# design.net
KiCad netlist of a schematic drawn in EasyEDA Pro
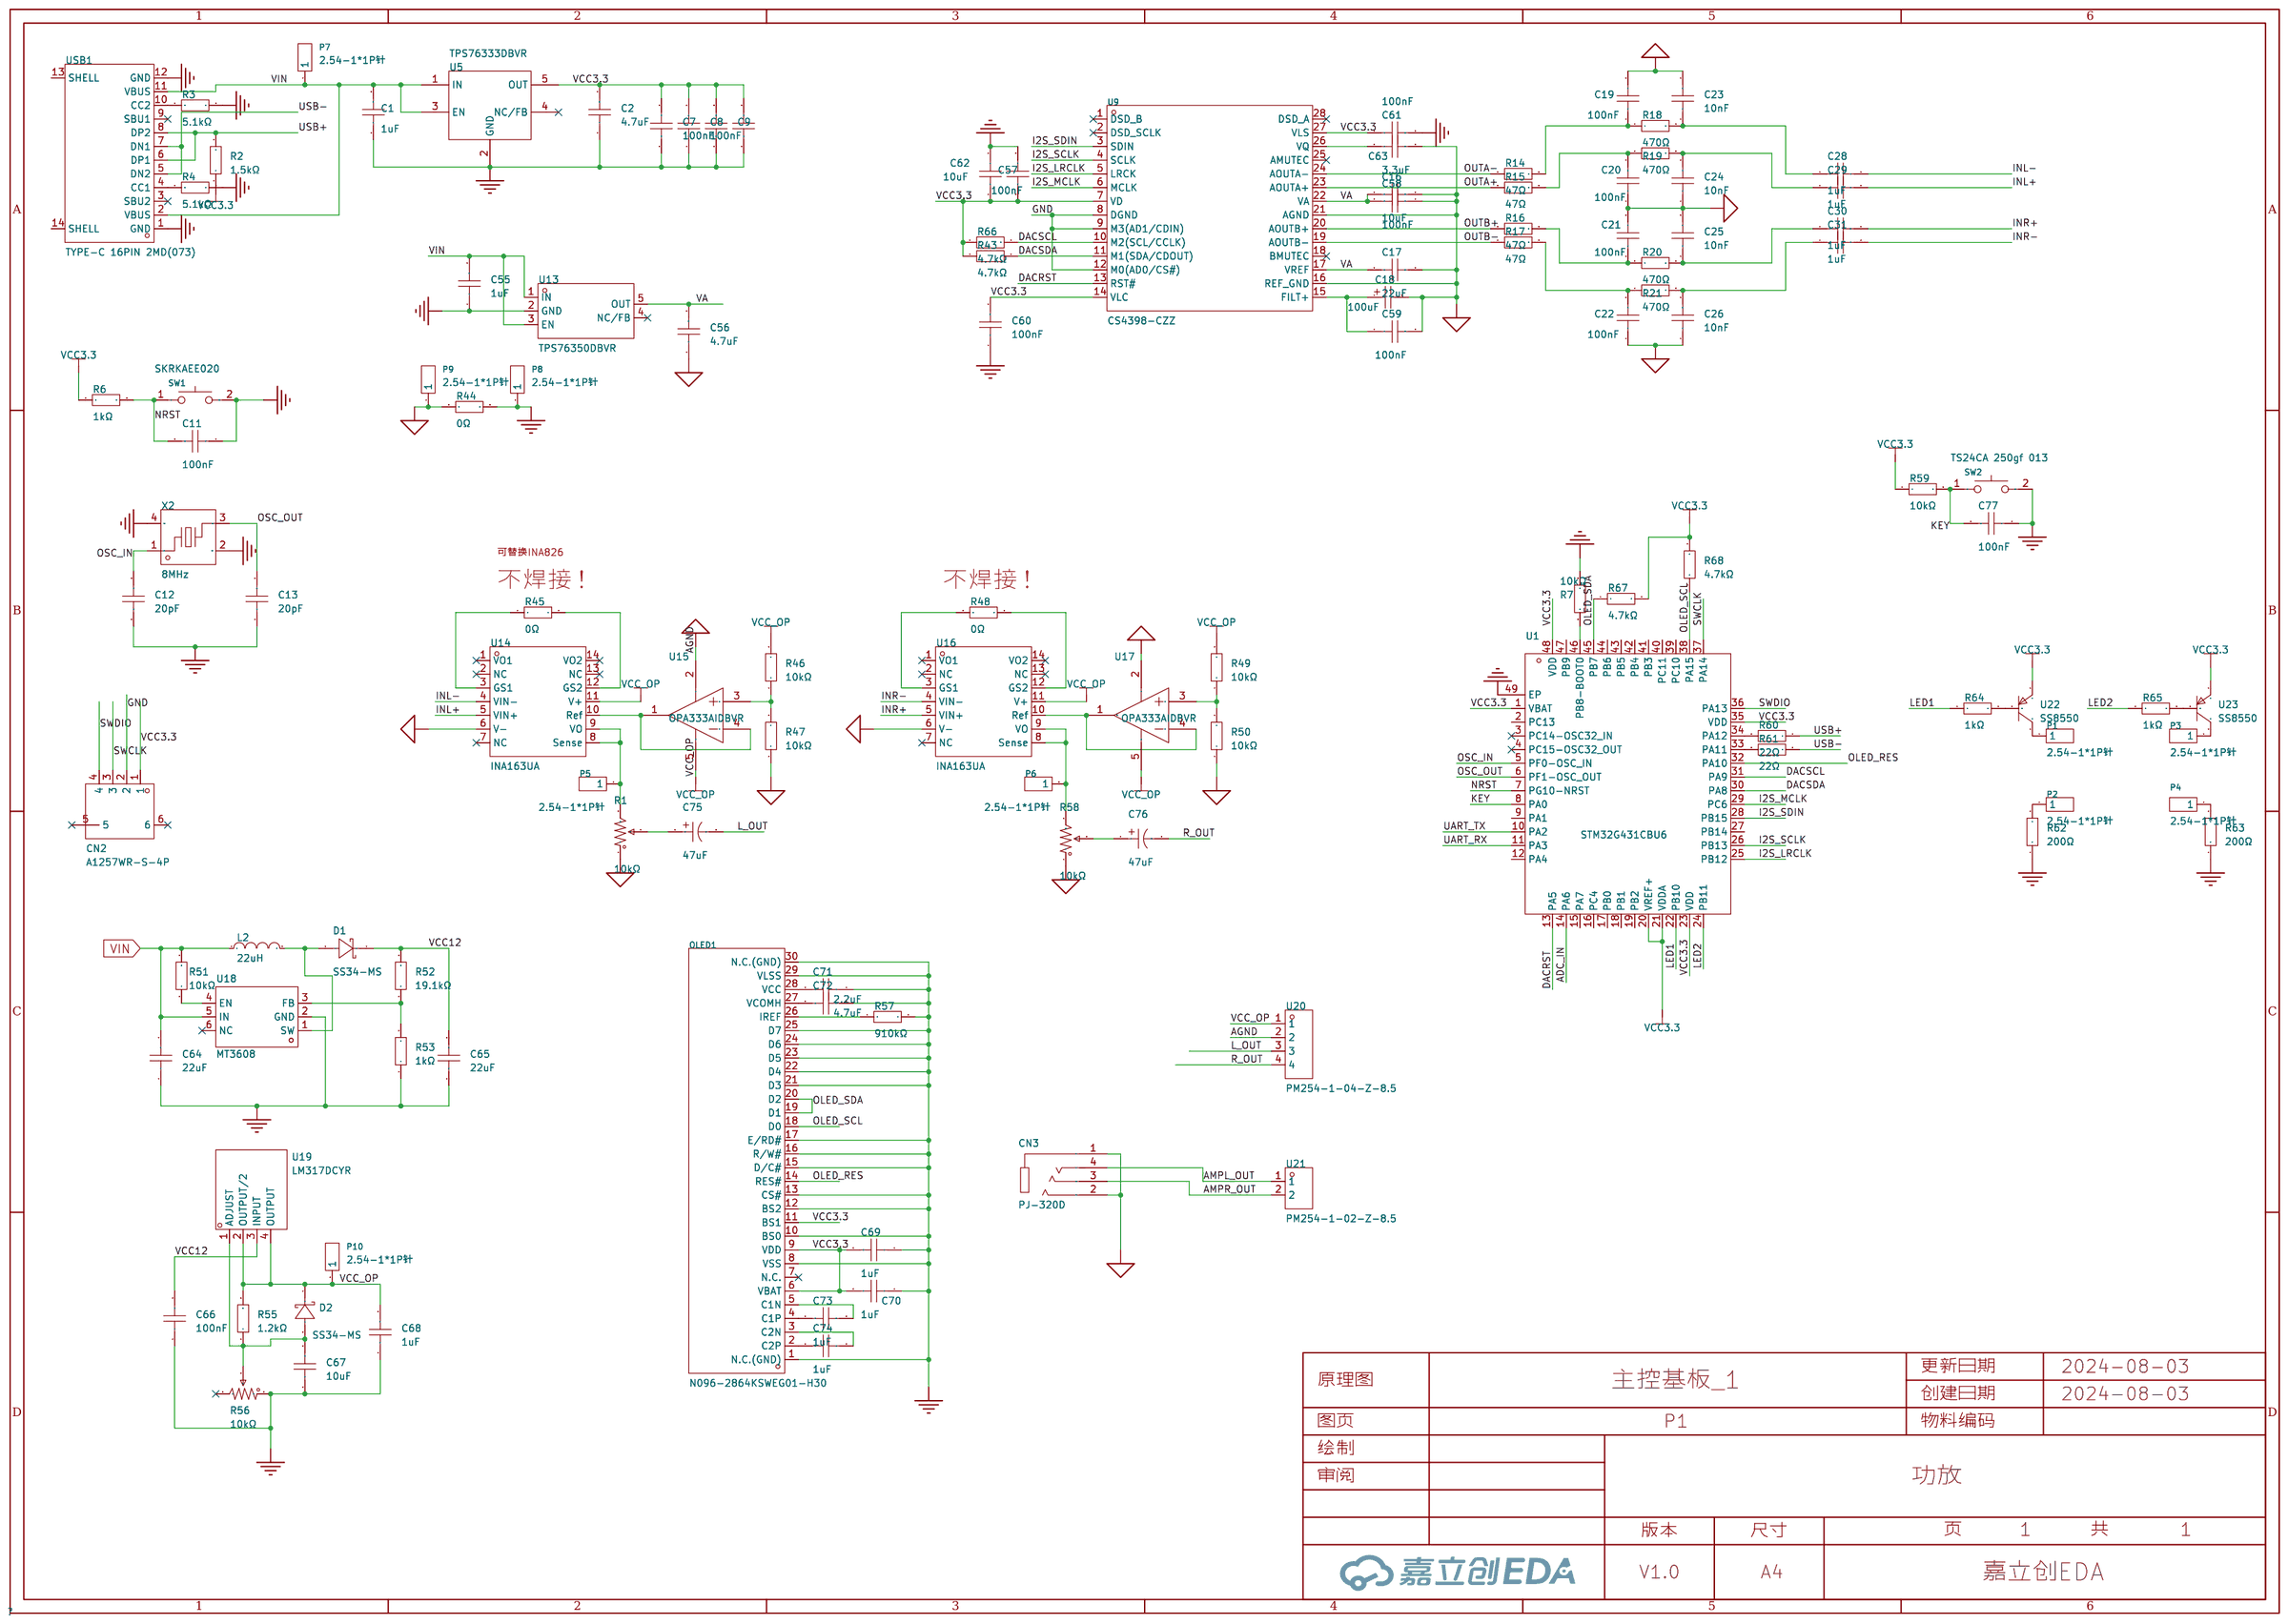
[diagram p0: schematic sheet]

(export (version "E")
  (design (tool "Eeschema 10.0.6"))
  (components
    (comp (ref "C1")
      (value "1uF")
      (fields
        (field (name "Manufacturer Part") "CL10A105KO8NNNC")
        (field (name "Manufacturer") "SAMSUNG(三星)")
      )
      (libsource (lib "easyedapro") (part "CapAcitance"))
    )
    (comp (ref "C2")
      (value "4.7uF")
      (fields
        (field (name "Manufacturer Part") "CL10A475KO8NNNC")
        (field (name "Manufacturer") "SAMSUNG(三星)")
      )
      (libsource (lib "easyedapro") (part "CapAcitance"))
    )
    (comp (ref "C7")
      (value "100nF")
      (fields
        (field (name "Manufacturer Part") "CC0603KRX7R9BB104")
        (field (name "Manufacturer") "YAGEO(国巨)")
      )
      (libsource (lib "easyedapro") (part "CapAcitance"))
    )
    (comp (ref "C8")
      (value "100nF")
      (fields
        (field (name "Manufacturer Part") "CC0603KRX7R9BB104")
        (field (name "Manufacturer") "YAGEO(国巨)")
      )
      (libsource (lib "easyedapro") (part "CapAcitance"))
    )
    (comp (ref "C9")
      (value "100nF")
      (fields
        (field (name "Manufacturer Part") "CC0603KRX7R9BB104")
        (field (name "Manufacturer") "YAGEO(国巨)")
      )
      (libsource (lib "easyedapro") (part "CapAcitance"))
    )
    (comp (ref "C10")
      (value "100nF")
      (fields
        (field (name "Manufacturer Part") "CC0603KRX7R9BB104")
        (field (name "Manufacturer") "YAGEO(国巨)")
      )
      (libsource (lib "easyedapro") (part "CapAcitance"))
    )
    (comp (ref "C11")
      (value "100nF")
      (fields
        (field (name "Manufacturer Part") "CC0603KRX7R9BB104")
        (field (name "Manufacturer") "YAGEO(国巨)")
      )
      (libsource (lib "easyedapro") (part "CapAcitance"))
    )
    (comp (ref "C12")
      (value "20pF")
      (fields
        (field (name "Manufacturer Part") "CC0603JRNPO9BN200")
        (field (name "Manufacturer") "YAGEO(国巨)")
      )
      (libsource (lib "easyedapro") (part "CapAcitance"))
    )
    (comp (ref "C13")
      (value "20pF")
      (fields
        (field (name "Manufacturer Part") "CC0603JRNPO9BN200")
        (field (name "Manufacturer") "YAGEO(国巨)")
      )
      (libsource (lib "easyedapro") (part "CapAcitance"))
    )
    (comp (ref "C16")
      (value "10uF")
      (fields
        (field (name "Manufacturer Part") "CL10A106KP8NNNC")
        (field (name "Manufacturer") "SAMSUNG(三星)")
      )
      (libsource (lib "easyedapro") (part "CapAcitance"))
    )
    (comp (ref "C17")
      (value "22uF")
      (fields
        (field (name "Manufacturer Part") "CL10A226MO7JZNC")
        (field (name "Manufacturer") "SAMSUNG(三星)")
      )
      (libsource (lib "easyedapro") (part "CapAcitance"))
    )
    (comp (ref "C18")
      (value "100uF")
      (fields
        (field (name "Manufacturer Part") "CA45-D-16V-100μF-K")
        (field (name "Manufacturer") "TORCH(火炬)")
      )
      (libsource (lib "easyedapro") (part "TAJD107K016RNJ"))
    )
    (comp (ref "C19")
      (value "100nF")
      (fields
        (field (name "Manufacturer Part") "CC0603KRX7R9BB104")
        (field (name "Manufacturer") "YAGEO(国巨)")
      )
      (libsource (lib "easyedapro") (part "CapAcitance"))
    )
    (comp (ref "C20")
      (value "100nF")
      (fields
        (field (name "Manufacturer Part") "CC0603KRX7R9BB104")
        (field (name "Manufacturer") "YAGEO(国巨)")
      )
      (libsource (lib "easyedapro") (part "CapAcitance"))
    )
    (comp (ref "C21")
      (value "100nF")
      (fields
        (field (name "Manufacturer Part") "CC0603KRX7R9BB104")
        (field (name "Manufacturer") "YAGEO(国巨)")
      )
      (libsource (lib "easyedapro") (part "CapAcitance"))
    )
    (comp (ref "C22")
      (value "100nF")
      (fields
        (field (name "Manufacturer Part") "CC0603KRX7R9BB104")
        (field (name "Manufacturer") "YAGEO(国巨)")
      )
      (libsource (lib "easyedapro") (part "CapAcitance"))
    )
    (comp (ref "C23")
      (value "10nF")
      (fields
        (field (name "Manufacturer Part") "CC0603KRX7R9BB103")
        (field (name "Manufacturer") "YAGEO(国巨)")
      )
      (libsource (lib "easyedapro") (part "CapAcitance"))
    )
    (comp (ref "C24")
      (value "10nF")
      (fields
        (field (name "Manufacturer Part") "CC0603KRX7R9BB103")
        (field (name "Manufacturer") "YAGEO(国巨)")
      )
      (libsource (lib "easyedapro") (part "CapAcitance"))
    )
    (comp (ref "C25")
      (value "10nF")
      (fields
        (field (name "Manufacturer Part") "CC0603KRX7R9BB103")
        (field (name "Manufacturer") "YAGEO(国巨)")
      )
      (libsource (lib "easyedapro") (part "CapAcitance"))
    )
    (comp (ref "C26")
      (value "10nF")
      (fields
        (field (name "Manufacturer Part") "CC0603KRX7R9BB103")
        (field (name "Manufacturer") "YAGEO(国巨)")
      )
      (libsource (lib "easyedapro") (part "CapAcitance"))
    )
    (comp (ref "C28")
      (value "1uF")
      (fields
        (field (name "Manufacturer Part") "CL10A105KO8NNNC")
        (field (name "Manufacturer") "SAMSUNG(三星)")
      )
      (libsource (lib "easyedapro") (part "CapAcitance"))
    )
    (comp (ref "C29")
      (value "1uF")
      (fields
        (field (name "Manufacturer Part") "CL10A105KO8NNNC")
        (field (name "Manufacturer") "SAMSUNG(三星)")
      )
      (libsource (lib "easyedapro") (part "CapAcitance"))
    )
    (comp (ref "C30")
      (value "1uF")
      (fields
        (field (name "Manufacturer Part") "CL10A105KO8NNNC")
        (field (name "Manufacturer") "SAMSUNG(三星)")
      )
      (libsource (lib "easyedapro") (part "CapAcitance"))
    )
    (comp (ref "C31")
      (value "1uF")
      (fields
        (field (name "Manufacturer Part") "CL10A105KO8NNNC")
        (field (name "Manufacturer") "SAMSUNG(三星)")
      )
      (libsource (lib "easyedapro") (part "CapAcitance"))
    )
    (comp (ref "C55")
      (value "1uF")
      (fields
        (field (name "Manufacturer Part") "CL10A105KO8NNNC")
        (field (name "Manufacturer") "SAMSUNG(三星)")
      )
      (libsource (lib "easyedapro") (part "CapAcitance"))
    )
    (comp (ref "C56")
      (value "4.7uF")
      (fields
        (field (name "Manufacturer Part") "CL10A475KO8NNNC")
        (field (name "Manufacturer") "SAMSUNG(三星)")
      )
      (libsource (lib "easyedapro") (part "CapAcitance"))
    )
    (comp (ref "C57")
      (value "100nF")
      (fields
        (field (name "Manufacturer Part") "CC0603KRX7R9BB104")
        (field (name "Manufacturer") "YAGEO(国巨)")
      )
      (libsource (lib "easyedapro") (part "CapAcitance"))
    )
    (comp (ref "C58")
      (value "100nF")
      (fields
        (field (name "Manufacturer Part") "CC0603KRX7R9BB104")
        (field (name "Manufacturer") "YAGEO(国巨)")
      )
      (libsource (lib "easyedapro") (part "CapAcitance"))
    )
    (comp (ref "C59")
      (value "100nF")
      (fields
        (field (name "Manufacturer Part") "CC0603KRX7R9BB104")
        (field (name "Manufacturer") "YAGEO(国巨)")
      )
      (libsource (lib "easyedapro") (part "CapAcitance"))
    )
    (comp (ref "C60")
      (value "100nF")
      (fields
        (field (name "Manufacturer Part") "CC0603KRX7R9BB104")
        (field (name "Manufacturer") "YAGEO(国巨)")
      )
      (libsource (lib "easyedapro") (part "CapAcitance"))
    )
    (comp (ref "C61")
      (value "100nF")
      (fields
        (field (name "Manufacturer Part") "CC0603KRX7R9BB104")
        (field (name "Manufacturer") "YAGEO(国巨)")
      )
      (libsource (lib "easyedapro") (part "CapAcitance"))
    )
    (comp (ref "C62")
      (value "10uF")
      (fields
        (field (name "Manufacturer Part") "CL10A106KP8NNNC")
        (field (name "Manufacturer") "SAMSUNG(三星)")
      )
      (libsource (lib "easyedapro") (part "CapAcitance"))
    )
    (comp (ref "C63")
      (value "3.3uF")
      (fields (field (name "Manufacturer Part") "C1608X5R1E335KT000E") (field (name "Manufacturer") "TDK"))
      (libsource (lib "easyedapro") (part "CapAcitance"))
    )
    (comp (ref "C64")
      (value "22uF")
      (fields
        (field (name "Manufacturer Part") "CL10A226MO7JZNC")
        (field (name "Manufacturer") "SAMSUNG(三星)")
      )
      (libsource (lib "easyedapro") (part "CapAcitance"))
    )
    (comp (ref "C65")
      (value "22uF")
      (fields
        (field (name "Manufacturer Part") "CL10A226MO7JZNC")
        (field (name "Manufacturer") "SAMSUNG(三星)")
      )
      (libsource (lib "easyedapro") (part "CapAcitance"))
    )
    (comp (ref "C66")
      (value "100nF")
      (fields
        (field (name "Manufacturer Part") "CC0603KRX7R9BB104")
        (field (name "Manufacturer") "YAGEO(国巨)")
      )
      (libsource (lib "easyedapro") (part "CapAcitance"))
    )
    (comp (ref "C67")
      (value "10uF")
      (fields
        (field (name "Manufacturer Part") "CL10A106MA8NRNC")
        (field (name "Manufacturer") "SAMSUNG(三星)")
      )
      (libsource (lib "easyedapro") (part "CapAcitance"))
    )
    (comp (ref "C68")
      (value "1uF")
      (fields
        (field (name "Manufacturer Part") "CL10A105KO8NNNC")
        (field (name "Manufacturer") "SAMSUNG(三星)")
      )
      (libsource (lib "easyedapro") (part "CapAcitance"))
    )
    (comp (ref "C69")
      (value "1uF")
      (fields
        (field (name "Manufacturer Part") "CL10A105KO8NNNC")
        (field (name "Manufacturer") "SAMSUNG(三星)")
      )
      (libsource (lib "easyedapro") (part "CapAcitance"))
    )
    (comp (ref "C70")
      (value "1uF")
      (fields
        (field (name "Manufacturer Part") "CL10A105KO8NNNC")
        (field (name "Manufacturer") "SAMSUNG(三星)")
      )
      (libsource (lib "easyedapro") (part "CapAcitance"))
    )
    (comp (ref "C71")
      (value "2.2uF")
      (fields
        (field (name "Manufacturer Part") "CL10A225KO8NNNC")
        (field (name "Manufacturer") "SAMSUNG(三星)")
      )
      (libsource (lib "easyedapro") (part "CapAcitance"))
    )
    (comp (ref "C72")
      (value "4.7uF")
      (fields
        (field (name "Manufacturer Part") "CL10A475KO8NNNC")
        (field (name "Manufacturer") "SAMSUNG(三星)")
      )
      (libsource (lib "easyedapro") (part "CapAcitance"))
    )
    (comp (ref "C73")
      (value "1uF")
      (fields
        (field (name "Manufacturer Part") "CL10A105KO8NNNC")
        (field (name "Manufacturer") "SAMSUNG(三星)")
      )
      (libsource (lib "easyedapro") (part "CapAcitance"))
    )
    (comp (ref "C74")
      (value "1uF")
      (fields
        (field (name "Manufacturer Part") "CL10A105KO8NNNC")
        (field (name "Manufacturer") "SAMSUNG(三星)")
      )
      (libsource (lib "easyedapro") (part "CapAcitance"))
    )
    (comp (ref "C75")
      (value "47uF")
      (footprint "easyedapro:CAP-SMD_BD5.0-L5.3-W5.3-LS6.0-FD")
      (description "容值:47uF;精度:±20%;额定电压:16V;纹波电流:31mA@120Hz;等效串联电阻:-;")
      (fields (field (name "Manufacturer Part") "RST47UF16V034") (field (name "Manufacturer") "KNSCHA(科尼盛)"))
      (libsource (lib "easyedapro") (part "RST47UF16V034"))
    )
    (comp (ref "C76")
      (value "47uF")
      (footprint "easyedapro:CAP-SMD_BD5.0-L5.3-W5.3-LS6.0-FD")
      (description "容值:47uF;精度:±20%;额定电压:16V;纹波电流:31mA@120Hz;等效串联电阻:-;")
      (fields (field (name "Manufacturer Part") "RST47UF16V034") (field (name "Manufacturer") "KNSCHA(科尼盛)"))
      (libsource (lib "easyedapro") (part "RST47UF16V034"))
    )
    (comp (ref "C77")
      (value "100nF")
      (fields
        (field (name "Manufacturer Part") "CC0603KRX7R9BB104")
        (field (name "Manufacturer") "YAGEO(国巨)")
      )
      (libsource (lib "easyedapro") (part "CapAcitance"))
    )
    (comp (ref "CN2")
      (value "A1257WR-S-4P")
      (footprint "easyedapro:CONN-SMD_A1257WR-S-4P")
      (description "插针结构:1x4P;间距:1.25mm;安装方式:-;行距:-;总PIN数:4P;排数:1;每排PIN数:4;参考系列:GH;触头材质:黄铜;")
      (fields (field (name "Manufacturer") "CJT(长江连接器)"))
      (libsource (lib "easyedapro") (part "A1257WR-S-4P"))
    )
    (comp (ref "CN3")
      (value "PJ-320D")
      (footprint "easyedapro:AUDIO-SMD_PJ-320D")
      (description "连接器类型:3.5mm耳机座;额定电流:300mA;额定电压:50V;工作温度范围:-16°C~+65°C;")
      (fields (field (name "Manufacturer") "SHOU HAN(首韩)"))
      (libsource (lib "easyedapro") (part "PJ-320D"))
    )
    (comp (ref "D1")
      (value "SS34-MS")
      (footprint "easyedapro:DO-214AC_L4.3-W2.7-LS5.0-RD")
      (description "二极管配置:-;正向压降(Vf):550mV@3A;直流反向耐压(Vr):40V;整流电流:3A;")
      (fields (field (name "Manufacturer") "MSKSEMI(美森科)"))
      (libsource (lib "easyedapro") (part "SS34-MS"))
    )
    (comp (ref "D2")
      (value "SS34-MS")
      (footprint "easyedapro:DO-214AC_L4.3-W2.7-LS5.0-RD")
      (description "二极管配置:-;正向压降(Vf):550mV@3A;直流反向耐压(Vr):40V;整流电流:3A;")
      (fields (field (name "Manufacturer") "MSKSEMI(美森科)"))
      (libsource (lib "easyedapro") (part "SS34-MS"))
    )
    (comp (ref "L2")
      (value "22uH")
      (footprint "easyedapro:IND-SMD_L3.0-W3.0_FNR30XXS")
      (description "电感值:22uH;精度:±20%;额定电流:690mA;饱和电流(Isat):680mA;")
      (fields (field (name "Manufacturer Part") "FNR3015S220MT") (field (name "Manufacturer") "cjiang(长江微电)"))
      (libsource (lib "easyedapro") (part "FNR3015S220MT"))
    )
    (comp (ref "OLED1")
      (value "N096-2864KSWEG01-H30")
      (footprint "easyedapro:OLED_0.96-30P-P0.70-12864")
      (description "主控芯片:SSD1306;尺寸(inch):0.96;")
      (fields (field (name "Manufacturer") "Newvision(新智景)"))
      (libsource (lib "easyedapro") (part "N096-2864KSWEG01-H30"))
    )
    (comp (ref "P1")
      (value "2.54-1*1P针")
      (footprint "easyedapro:HDR-TH_1P-P2.54-V-M")
      (description "插针结构:-;间距:-;行距:-;圆针/方针:-;安装类型:直插;排数:单排;总PIN位数:1P;额定电流:-;额定电压:-;配合针长度:-;塑高:-;触头材质:-;触头镀层:-;颜色:黑色;")
      (fields (field (name "Manufacturer") "BOOMELE(博穆精密)"))
      (libsource (lib "easyedapro") (part "Header-Male-2.54_1x1"))
    )
    (comp (ref "P2")
      (value "2.54-1*1P针")
      (footprint "easyedapro:HDR-TH_1P-P2.54-V-M")
      (description "插针结构:-;间距:-;行距:-;圆针/方针:-;安装类型:直插;排数:单排;总PIN位数:1P;额定电流:-;额定电压:-;配合针长度:-;塑高:-;触头材质:-;触头镀层:-;颜色:黑色;")
      (fields (field (name "Manufacturer") "BOOMELE(博穆精密)"))
      (libsource (lib "easyedapro") (part "Header-Male-2.54_1x1"))
    )
    (comp (ref "P3")
      (value "2.54-1*1P针")
      (footprint "easyedapro:HDR-TH_1P-P2.54-V-M")
      (description "插针结构:-;间距:-;行距:-;圆针/方针:-;安装类型:直插;排数:单排;总PIN位数:1P;额定电流:-;额定电压:-;配合针长度:-;塑高:-;触头材质:-;触头镀层:-;颜色:黑色;")
      (fields (field (name "Manufacturer") "BOOMELE(博穆精密)"))
      (libsource (lib "easyedapro") (part "Header-Male-2.54_1x1"))
    )
    (comp (ref "P4")
      (value "2.54-1*1P针")
      (footprint "easyedapro:HDR-TH_1P-P2.54-V-M")
      (description "插针结构:-;间距:-;行距:-;圆针/方针:-;安装类型:直插;排数:单排;总PIN位数:1P;额定电流:-;额定电压:-;配合针长度:-;塑高:-;触头材质:-;触头镀层:-;颜色:黑色;")
      (fields (field (name "Manufacturer") "BOOMELE(博穆精密)"))
      (libsource (lib "easyedapro") (part "Header-Male-2.54_1x1"))
    )
    (comp (ref "P5")
      (value "2.54-1*1P针")
      (footprint "easyedapro:HDR-TH_1P-P2.54-V-M")
      (description "插针结构:-;间距:-;行距:-;圆针/方针:-;安装类型:直插;排数:单排;总PIN位数:1P;额定电流:-;额定电压:-;配合针长度:-;塑高:-;触头材质:-;触头镀层:-;颜色:黑色;")
      (fields (field (name "Manufacturer") "BOOMELE(博穆精密)"))
      (libsource (lib "easyedapro") (part "Header-Male-2.54_1x1"))
    )
    (comp (ref "P6")
      (value "2.54-1*1P针")
      (footprint "easyedapro:HDR-TH_1P-P2.54-V-M")
      (description "插针结构:-;间距:-;行距:-;圆针/方针:-;安装类型:直插;排数:单排;总PIN位数:1P;额定电流:-;额定电压:-;配合针长度:-;塑高:-;触头材质:-;触头镀层:-;颜色:黑色;")
      (fields (field (name "Manufacturer") "BOOMELE(博穆精密)"))
      (libsource (lib "easyedapro") (part "Header-Male-2.54_1x1"))
    )
    (comp (ref "P7")
      (value "2.54-1*1P针")
      (footprint "easyedapro:HDR-TH_1P-P2.54-V-M")
      (description "插针结构:-;间距:-;行距:-;圆针/方针:-;安装类型:直插;排数:单排;总PIN位数:1P;额定电流:-;额定电压:-;配合针长度:-;塑高:-;触头材质:-;触头镀层:-;颜色:黑色;")
      (fields (field (name "Manufacturer") "BOOMELE(博穆精密)"))
      (libsource (lib "easyedapro") (part "Header-Male-2.54_1x1"))
    )
    (comp (ref "P8")
      (value "2.54-1*1P针")
      (footprint "easyedapro:HDR-TH_1P-P2.54-V-M")
      (description "插针结构:-;间距:-;行距:-;圆针/方针:-;安装类型:直插;排数:单排;总PIN位数:1P;额定电流:-;额定电压:-;配合针长度:-;塑高:-;触头材质:-;触头镀层:-;颜色:黑色;")
      (fields (field (name "Manufacturer") "BOOMELE(博穆精密)"))
      (libsource (lib "easyedapro") (part "Header-Male-2.54_1x1"))
    )
    (comp (ref "P9")
      (value "2.54-1*1P针")
      (footprint "easyedapro:HDR-TH_1P-P2.54-V-M")
      (description "插针结构:-;间距:-;行距:-;圆针/方针:-;安装类型:直插;排数:单排;总PIN位数:1P;额定电流:-;额定电压:-;配合针长度:-;塑高:-;触头材质:-;触头镀层:-;颜色:黑色;")
      (fields (field (name "Manufacturer") "BOOMELE(博穆精密)"))
      (libsource (lib "easyedapro") (part "Header-Male-2.54_1x1"))
    )
    (comp (ref "P10")
      (value "2.54-1*1P针")
      (footprint "easyedapro:HDR-TH_1P-P2.54-V-M")
      (description "插针结构:-;间距:-;行距:-;圆针/方针:-;安装类型:直插;排数:单排;总PIN位数:1P;额定电流:-;额定电压:-;配合针长度:-;塑高:-;触头材质:-;触头镀层:-;颜色:黑色;")
      (fields (field (name "Manufacturer") "BOOMELE(博穆精密)"))
      (libsource (lib "easyedapro") (part "Header-Male-2.54_1x1"))
    )
    (comp (ref "R1")
      (value "10kΩ")
      (footprint "easyedapro:RES-ADJ-SMD_3P-L3.0-W3.8-P1.75-BR")
      (description "阻值:10kΩ;精度:±25%;功率:150mW;温度系数:±250ppm/°C;")
      (fields (field (name "Manufacturer Part") "TC33X-2-103E") (field (name "Manufacturer") "BOURNS"))
      (libsource (lib "easyedapro") (part "TC33X-2-103E"))
    )
    (comp (ref "R2")
      (value "1.5kΩ")
      (fields (field (name "Manufacturer Part") "FRC0603F1501TS") (field (name "Manufacturer") "FOJAN(富捷)"))
      (libsource (lib "easyedapro") (part "电阻"))
    )
    (comp (ref "R3")
      (value "5.1kΩ")
      (fields (field (name "Manufacturer Part") "FRC0603F5101TS") (field (name "Manufacturer") "FOJAN(富捷)"))
      (libsource (lib "easyedapro") (part "电阻"))
    )
    (comp (ref "R4")
      (value "5.1kΩ")
      (fields (field (name "Manufacturer Part") "FRC0603F5101TS") (field (name "Manufacturer") "FOJAN(富捷)"))
      (libsource (lib "easyedapro") (part "电阻"))
    )
    (comp (ref "R6")
      (value "1kΩ")
      (fields
        (field (name "Manufacturer Part") "0603WAF1001T5E")
        (field (name "Manufacturer") "UNI-ROYAL(厚声)")
      )
      (libsource (lib "easyedapro") (part "电阻"))
    )
    (comp (ref "R7")
      (value "10kΩ")
      (fields
        (field (name "Manufacturer Part") "0603WAF1002T5E")
        (field (name "Manufacturer") "UNI-ROYAL(厚声)")
      )
      (libsource (lib "easyedapro") (part "电阻"))
    )
    (comp (ref "R14")
      (value "47Ω")
      (fields
        (field (name "Manufacturer Part") "0603WAJ0470T5E")
        (field (name "Manufacturer") "UNI-ROYAL(厚声)")
      )
      (libsource (lib "easyedapro") (part "电阻"))
    )
    (comp (ref "R15")
      (value "47Ω")
      (fields
        (field (name "Manufacturer Part") "0603WAJ0470T5E")
        (field (name "Manufacturer") "UNI-ROYAL(厚声)")
      )
      (libsource (lib "easyedapro") (part "电阻"))
    )
    (comp (ref "R16")
      (value "47Ω")
      (fields
        (field (name "Manufacturer Part") "0603WAJ0470T5E")
        (field (name "Manufacturer") "UNI-ROYAL(厚声)")
      )
      (libsource (lib "easyedapro") (part "电阻"))
    )
    (comp (ref "R17")
      (value "47Ω")
      (fields
        (field (name "Manufacturer Part") "0603WAJ0470T5E")
        (field (name "Manufacturer") "UNI-ROYAL(厚声)")
      )
      (libsource (lib "easyedapro") (part "电阻"))
    )
    (comp (ref "R18")
      (value "470Ω")
      (fields
        (field (name "Manufacturer Part") "0603WAJ0471T5E")
        (field (name "Manufacturer") "UNI-ROYAL(厚声)")
      )
      (libsource (lib "easyedapro") (part "电阻"))
    )
    (comp (ref "R19")
      (value "470Ω")
      (fields
        (field (name "Manufacturer Part") "0603WAJ0471T5E")
        (field (name "Manufacturer") "UNI-ROYAL(厚声)")
      )
      (libsource (lib "easyedapro") (part "电阻"))
    )
    (comp (ref "R20")
      (value "470Ω")
      (fields
        (field (name "Manufacturer Part") "0603WAJ0471T5E")
        (field (name "Manufacturer") "UNI-ROYAL(厚声)")
      )
      (libsource (lib "easyedapro") (part "电阻"))
    )
    (comp (ref "R21")
      (value "470Ω")
      (fields
        (field (name "Manufacturer Part") "0603WAJ0471T5E")
        (field (name "Manufacturer") "UNI-ROYAL(厚声)")
      )
      (libsource (lib "easyedapro") (part "电阻"))
    )
    (comp (ref "R43")
      (value "4.7kΩ")
      (fields (field (name "Manufacturer Part") "RC0603FR-074K7L") (field (name "Manufacturer") "YAGEO(国巨)"))
      (libsource (lib "easyedapro") (part "电阻"))
    )
    (comp (ref "R44")
      (value "0Ω")
      (fields
        (field (name "Manufacturer Part") "0603WAF0000T5E")
        (field (name "Manufacturer") "UNI-ROYAL(厚声)")
      )
      (libsource (lib "easyedapro") (part "电阻"))
    )
    (comp (ref "R45")
      (value "0Ω")
      (fields
        (field (name "Manufacturer Part") "0603WAF0000T5E")
        (field (name "Manufacturer") "UNI-ROYAL(厚声)")
      )
      (libsource (lib "easyedapro") (part "电阻"))
    )
    (comp (ref "R46")
      (value "10kΩ")
      (fields
        (field (name "Manufacturer Part") "0603WAF1002T5E")
        (field (name "Manufacturer") "UNI-ROYAL(厚声)")
      )
      (libsource (lib "easyedapro") (part "电阻"))
    )
    (comp (ref "R47")
      (value "10kΩ")
      (fields
        (field (name "Manufacturer Part") "0603WAF1002T5E")
        (field (name "Manufacturer") "UNI-ROYAL(厚声)")
      )
      (libsource (lib "easyedapro") (part "电阻"))
    )
    (comp (ref "R48")
      (value "0Ω")
      (fields
        (field (name "Manufacturer Part") "0603WAF0000T5E")
        (field (name "Manufacturer") "UNI-ROYAL(厚声)")
      )
      (libsource (lib "easyedapro") (part "电阻"))
    )
    (comp (ref "R49")
      (value "10kΩ")
      (fields
        (field (name "Manufacturer Part") "0603WAF1002T5E")
        (field (name "Manufacturer") "UNI-ROYAL(厚声)")
      )
      (libsource (lib "easyedapro") (part "电阻"))
    )
    (comp (ref "R50")
      (value "10kΩ")
      (fields
        (field (name "Manufacturer Part") "0603WAF1002T5E")
        (field (name "Manufacturer") "UNI-ROYAL(厚声)")
      )
      (libsource (lib "easyedapro") (part "电阻"))
    )
    (comp (ref "R51")
      (value "10kΩ")
      (fields
        (field (name "Manufacturer Part") "0603WAF1002T5E")
        (field (name "Manufacturer") "UNI-ROYAL(厚声)")
      )
      (libsource (lib "easyedapro") (part "电阻"))
    )
    (comp (ref "R52")
      (value "19.1kΩ")
      (fields
        (field (name "Manufacturer Part") "0603WAF1912T5E")
        (field (name "Manufacturer") "UNI-ROYAL(厚声)")
      )
      (libsource (lib "easyedapro") (part "电阻"))
    )
    (comp (ref "R53")
      (value "1kΩ")
      (fields
        (field (name "Manufacturer Part") "0603WAF1001T5E")
        (field (name "Manufacturer") "UNI-ROYAL(厚声)")
      )
      (libsource (lib "easyedapro") (part "电阻"))
    )
    (comp (ref "R55")
      (value "1.2kΩ")
      (fields
        (field (name "Manufacturer Part") "0603WAF1201T5E")
        (field (name "Manufacturer") "UNI-ROYAL(厚声)")
      )
      (libsource (lib "easyedapro") (part "电阻"))
    )
    (comp (ref "R56")
      (value "10kΩ")
      (footprint "easyedapro:RES-ADJ-SMD_3P-L3.0-W3.8-P1.75-BR")
      (description "阻值:10kΩ;精度:±25%;功率:150mW;温度系数:±250ppm/°C;")
      (fields (field (name "Manufacturer Part") "TC33X-2-103E") (field (name "Manufacturer") "BOURNS"))
      (libsource (lib "easyedapro") (part "TC33X-2-103E"))
    )
    (comp (ref "R57")
      (value "910kΩ")
      (fields
        (field (name "Manufacturer Part") "0603WAF9103T5E")
        (field (name "Manufacturer") "UNI-ROYAL(厚声)")
      )
      (libsource (lib "easyedapro") (part "电阻"))
    )
    (comp (ref "R58")
      (value "10kΩ")
      (footprint "easyedapro:RES-ADJ-SMD_3P-L3.0-W3.8-P1.75-BR")
      (description "阻值:10kΩ;精度:±25%;功率:150mW;温度系数:±250ppm/°C;")
      (fields (field (name "Manufacturer Part") "TC33X-2-103E") (field (name "Manufacturer") "BOURNS"))
      (libsource (lib "easyedapro") (part "TC33X-2-103E"))
    )
    (comp (ref "R59")
      (value "10kΩ")
      (fields
        (field (name "Manufacturer Part") "0603WAF1002T5E")
        (field (name "Manufacturer") "UNI-ROYAL(厚声)")
      )
      (libsource (lib "easyedapro") (part "电阻"))
    )
    (comp (ref "R60")
      (value "22Ω")
      (fields
        (field (name "Manufacturer Part") "0603WAF220JT5E")
        (field (name "Manufacturer") "UNI-ROYAL(厚声)")
      )
      (libsource (lib "easyedapro") (part "电阻"))
    )
    (comp (ref "R61")
      (value "22Ω")
      (fields
        (field (name "Manufacturer Part") "0603WAF220JT5E")
        (field (name "Manufacturer") "UNI-ROYAL(厚声)")
      )
      (libsource (lib "easyedapro") (part "电阻"))
    )
    (comp (ref "R62")
      (value "200Ω")
      (fields
        (field (name "Manufacturer Part") "0603WAF2000T5E")
        (field (name "Manufacturer") "UNI-ROYAL(厚声)")
      )
      (libsource (lib "easyedapro") (part "电阻"))
    )
    (comp (ref "R63")
      (value "200Ω")
      (fields
        (field (name "Manufacturer Part") "0603WAF2000T5E")
        (field (name "Manufacturer") "UNI-ROYAL(厚声)")
      )
      (libsource (lib "easyedapro") (part "电阻"))
    )
    (comp (ref "R64")
      (value "1kΩ")
      (fields
        (field (name "Manufacturer Part") "0603WAF1001T5E")
        (field (name "Manufacturer") "UNI-ROYAL(厚声)")
      )
      (libsource (lib "easyedapro") (part "电阻"))
    )
    (comp (ref "R65")
      (value "1kΩ")
      (fields
        (field (name "Manufacturer Part") "0603WAF1001T5E")
        (field (name "Manufacturer") "UNI-ROYAL(厚声)")
      )
      (libsource (lib "easyedapro") (part "电阻"))
    )
    (comp (ref "R66")
      (value "4.7kΩ")
      (fields (field (name "Manufacturer Part") "RC0603FR-074K7L") (field (name "Manufacturer") "YAGEO(国巨)"))
      (libsource (lib "easyedapro") (part "电阻"))
    )
    (comp (ref "R67")
      (value "4.7kΩ")
      (fields (field (name "Manufacturer Part") "RC0603FR-074K7L") (field (name "Manufacturer") "YAGEO(国巨)"))
      (libsource (lib "easyedapro") (part "电阻"))
    )
    (comp (ref "R68")
      (value "4.7kΩ")
      (fields (field (name "Manufacturer Part") "RC0603FR-074K7L") (field (name "Manufacturer") "YAGEO(国巨)"))
      (libsource (lib "easyedapro") (part "电阻"))
    )
    (comp (ref "SW1")
      (value "SKRKAEE020")
      (footprint "easyedapro:SW-SMD_L3.9-W3.0-P4.45")
      (description "电路结构:单刀单掷;按钮形状:圆形按钮;安装方式:立贴;开关长度:3.9mm;开关宽度:2.9mm;开关高度:2mm;触点电流:50mA;额定电压(DC):12V;带灯:-;机械寿命:-;")
      (fields (field (name "Manufacturer") "ALPSALPINE(阿尔卑斯阿尔派)"))
      (libsource (lib "easyedapro") (part "SKRKAEE020"))
    )
    (comp (ref "SW2")
      (value "TS24CA 250gf 013")
      (footprint "easyedapro:SW-SMD_L3.9-W3.0-P4.45")
      (description "电路结构:单刀单掷;按钮形状:圆形按钮;安装方式:立贴;开关长度:3.9mm;开关宽度:2.9mm;开关高度:2mm;触点电流:50mA;额定电压(DC):12V;带灯:-;机械寿命:-;")
      (fields (field (name "Manufacturer") "SHOU HAN(首韩)"))
      (libsource (lib "easyedapro") (part "SKRKAEE020"))
    )
    (comp (ref "U1")
      (value "STM32G431CBU6")
      (footprint "easyedapro:UFQFPN-48_L7.0-W7.0-P0.50-BL-EP")
      (description "CPU内核:ARM-M系列;程序存储容量:128KB;RAM总容量:32KB;GPIO端口数量:42;工作电压范围:1.71V~3.6V;CPU最大主频:170MHz;程序存储器类型:FLASH;")
      (fields (field (name "Manufacturer") "ST(意法半导体)"))
      (libsource (lib "easyedapro") (part "STM32G431CBU6"))
    )
    (comp (ref "U5")
      (value "TPS76333DBVR")
      (footprint "easyedapro:SOT-23-5_L3.0-W1.7-P0.95-LS2.8-BR")
      (description "输出类型:固定;最大输入电压:10V;输出电流:150mA;输出电压（最小值/固定值）:3.3V;")
      (fields (field (name "Manufacturer") "TI(德州仪器)"))
      (libsource (lib "easyedapro") (part "TPS76333DBVR"))
    )
    (comp (ref "U9")
      (value "CS4398-CZZ")
      (footprint "easyedapro:TSSOP-28_L9.7-W4.4-P0.65-LS6.4-BL")
      (description "接口类型:PCM；DSD;供电电压:3.1V~5.25V;分辨率(位):24;")
      (fields (field (name "Manufacturer") "Cirrus Logic(凌云)"))
      (libsource (lib "easyedapro") (part "CS4398-CZZ"))
    )
    (comp (ref "U13")
      (value "TPS76350DBVR")
      (footprint "easyedapro:SOT-23-5_L3.0-W1.7-P0.95-LS2.8-BR")
      (description "输出类型:固定;最大输入电压:10V;输出电压:5V;最大输出电流:150mA;电源纹波抑制比(PSRR):60dB@(1kHz);输出极性:正极;")
      (fields (field (name "Manufacturer") "TI(德州仪器)"))
      (libsource (lib "easyedapro") (part "TPS76350DBVR"))
    )
    (comp (ref "U14")
      (value "INA163UA")
      (footprint "easyedapro:SOIC-14_L8.7-W3.9-P1.27-LS6.0-BL")
      (description "放大器数:单路;输入偏置电流(Ib):2uA;输入失调电压(Vos):50uV;增益带宽积(GBP):-;压摆率(SR):15V/us;带宽(-3db):800kHz;")
      (fields (field (name "Manufacturer") "TI(德州仪器)"))
      (libsource (lib "easyedapro") (part "INA163UA"))
    )
    (comp (ref "U15")
      (value "OPA333AIDBVR")
      (fields (field (name "Manufacturer") "TI(德州仪器)"))
      (libsource (lib "easyedapro") (part "OPA237NA/3K"))
    )
    (comp (ref "U16")
      (value "INA163UA")
      (footprint "easyedapro:SOIC-14_L8.7-W3.9-P1.27-LS6.0-BL")
      (description "放大器数:单路;输入偏置电流(Ib):2uA;输入失调电压(Vos):50uV;增益带宽积(GBP):-;压摆率(SR):15V/us;带宽(-3db):800kHz;")
      (fields (field (name "Manufacturer") "TI(德州仪器)"))
      (libsource (lib "easyedapro") (part "INA163UA"))
    )
    (comp (ref "U17")
      (value "OPA333AIDBVR")
      (fields (field (name "Manufacturer") "TI(德州仪器)"))
      (libsource (lib "easyedapro") (part "OPA237NA/3K"))
    )
    (comp (ref "U18")
      (value "MT3608")
      (footprint "easyedapro:SOT-23-6_L2.9-W1.6-P0.95-LS2.8-BL")
      (description "功能类型:升压型;输入电压:2V~24V;输出电压:28V;输出电流(最大值):-;")
      (fields (field (name "Manufacturer") "西安航天民芯"))
      (libsource (lib "easyedapro") (part "MT3608"))
    )
    (comp (ref "U19")
      (value "LM317DCYR")
      (footprint "easyedapro:SOT-223-3_L6.5-W3.4-P2.30-LS7.0-BR")
      (description "输出类型:可调;最大输入电压:40V;输出电压:1.25V~37V;最大输出电流:1.5A;输出极性:正极;")
      (fields (field (name "Manufacturer") "TI(德州仪器)"))
      (libsource (lib "easyedapro") (part "LM317DCYR"))
    )
    (comp (ref "U20")
      (value "PM254-1-04-Z-8.5")
      (footprint "easyedapro:HDR-TH_4P-P2.54-V-F")
      (fields (field (name "Manufacturer") "HCTL(华灿天禄)"))
      (libsource (lib "easyedapro") (part "PM254-1-04-Z-8.5"))
    )
    (comp (ref "U21")
      (value "PM254-1-02-Z-8.5")
      (footprint "easyedapro:HDR-TH_2P-P2.54-V-F")
      (fields (field (name "Manufacturer") "HCTL(华灿天禄)"))
      (libsource (lib "easyedapro") (part "PM254-1-02-Z-8.5"))
    )
    (comp (ref "U22")
      (value "SS8550")
      (footprint "easyedapro:SOT-23-3_L2.9-W1.3-P1.90-LS2.4-BR")
      (description "晶体管类型:PNP;集电极电流(Ic):1.5A;集射极击穿电压(Vceo):25V;功率(Pd):300mW;直流电流增益(hFE@Ic,Vce):120@100mA,1.0V;")
      (fields (field (name "Manufacturer") "宏迦橙"))
      (libsource (lib "easyedapro") (part "SS8550_C7420371"))
    )
    (comp (ref "U23")
      (value "SS8550")
      (footprint "easyedapro:SOT-23-3_L2.9-W1.3-P1.90-LS2.4-BR")
      (description "晶体管类型:PNP;集电极电流(Ic):1.5A;集射极击穿电压(Vceo):25V;功率(Pd):300mW;直流电流增益(hFE@Ic,Vce):120@100mA,1.0V;")
      (fields (field (name "Manufacturer") "宏迦橙"))
      (libsource (lib "easyedapro") (part "SS8550_C7420371"))
    )
    (comp (ref "USB1")
      (value "TYPE-C 16PIN 2MD(073)")
      (footprint "easyedapro:USB-C-SMD_TYPE-C-6PIN-2MD-073")
      (description "连接器类型:Type-C;标准:-;公母:母;端口数量:1;触点数量:16P;安装方式:卧贴;额定电流 - 电源:5A;工作温度范围:-25°C~+85°C;")
      (fields (field (name "Manufacturer") "SHOU HAN(首韩)"))
      (libsource (lib "easyedapro") (part "TYPE-C 16PIN 2MD(073)"))
    )
    (comp (ref "X2")
      (value "8MHz")
      (footprint "easyedapro:CRYSTAL-SMD_4P-L3.2-W2.5-BL")
      (description "晶振类型:贴片晶振;频率:8MHz;常温频差:±10ppm;外接负载电容:20pF;频率稳定度(全温):±20ppm;")
      (fields (field (name "Manufacturer Part") "X32258MSB4SI") (field (name "Manufacturer") "YXC(扬兴晶振)"))
      (libsource (lib "easyedapro") (part "X32258MSB4SI"))
    )
  )
  (nets
    (net (code "1") (name "/ADC_IN") (class "Default")
      (node (ref "U1") (pin "14") (pinfunction "PA6_14") (pintype "unspecified"))
    )
    (net (code "2") (name "/AMPL_OUT") (class "Default")
      (node (ref "CN3") (pin "4") (pinfunction "4_4") (pintype "unspecified"))
      (node (ref "U21") (pin "1") (pinfunction "1_1") (pintype "unspecified"))
    )
    (net (code "3") (name "/AMPR_OUT") (class "Default")
      (node (ref "CN3") (pin "3") (pinfunction "3_3") (pintype "unspecified"))
      (node (ref "U21") (pin "2") (pinfunction "2_2") (pintype "unspecified"))
    )
    (net (code "4") (name "/DACRST") (class "Default")
      (node (ref "U1") (pin "13") (pinfunction "PA5_13") (pintype "unspecified"))
      (node (ref "U9") (pin "13") (pinfunction "RST#_13") (pintype "input"))
    )
    (net (code "5") (name "/DACSCL") (class "Default")
      (node (ref "R66") (pin "2") (pinfunction "2_2") (pintype "input"))
      (node (ref "U1") (pin "31") (pinfunction "PA9_31") (pintype "unspecified"))
      (node (ref "U9") (pin "10") (pinfunction "M2(SCL/CCLK)_10") (pintype "input"))
    )
    (net (code "6") (name "/DACSDA") (class "Default")
      (node (ref "R43") (pin "2") (pinfunction "2_2") (pintype "input"))
      (node (ref "U1") (pin "30") (pinfunction "PA8_30") (pintype "unspecified"))
      (node (ref "U9") (pin "11") (pinfunction "M1(SDA/CDOUT)_11") (pintype "input"))
    )
    (net (code "7") (name "/I2S_LRCLK") (class "Default")
      (node (ref "U1") (pin "25") (pinfunction "PB12_25") (pintype "unspecified"))
      (node (ref "U9") (pin "5") (pinfunction "LRCK_5") (pintype "input"))
    )
    (net (code "8") (name "/I2S_MCLK") (class "Default")
      (node (ref "U1") (pin "29") (pinfunction "PC6_29") (pintype "unspecified"))
      (node (ref "U9") (pin "6") (pinfunction "MCLK_6") (pintype "input"))
    )
    (net (code "9") (name "/I2S_SCLK") (class "Default")
      (node (ref "U1") (pin "26") (pinfunction "PB13_26") (pintype "unspecified"))
      (node (ref "U9") (pin "4") (pinfunction "SCLK_4") (pintype "input"))
    )
    (net (code "10") (name "/I2S_SDIN") (class "Default")
      (node (ref "U1") (pin "28") (pinfunction "PB15_28") (pintype "unspecified"))
      (node (ref "U9") (pin "3") (pinfunction "SDIN_3") (pintype "input"))
    )
    (net (code "11") (name "/INL+") (class "Default")
      (node (ref "C29") (pin "2") (pinfunction "2_2") (pintype "input"))
      (node (ref "U14") (pin "5") (pinfunction "VIN+_5") (pintype "unspecified"))
    )
    (net (code "12") (name "/INL-") (class "Default")
      (node (ref "C28") (pin "2") (pinfunction "2_2") (pintype "input"))
      (node (ref "U14") (pin "4") (pinfunction "VIN-_4") (pintype "unspecified"))
    )
    (net (code "13") (name "/INR+") (class "Default")
      (node (ref "C30") (pin "2") (pinfunction "2_2") (pintype "input"))
      (node (ref "U16") (pin "5") (pinfunction "VIN+_5") (pintype "unspecified"))
    )
    (net (code "14") (name "/INR-") (class "Default")
      (node (ref "C31") (pin "2") (pinfunction "2_2") (pintype "input"))
      (node (ref "U16") (pin "4") (pinfunction "VIN-_4") (pintype "unspecified"))
    )
    (net (code "15") (name "/KEY") (class "Default")
      (node (ref "C77") (pin "2") (pinfunction "2_2") (pintype "input"))
      (node (ref "R59") (pin "2") (pinfunction "2_2") (pintype "input"))
      (node (ref "SW2") (pin "1") (pinfunction "1_1") (pintype "input"))
      (node (ref "U1") (pin "8") (pinfunction "PA0_8") (pintype "unspecified"))
    )
    (net (code "16") (name "/LED1") (class "Default")
      (node (ref "R64") (pin "1") (pinfunction "1_1") (pintype "input"))
      (node (ref "U1") (pin "22") (pinfunction "PB10_22") (pintype "unspecified"))
    )
    (net (code "17") (name "/LED2") (class "Default")
      (node (ref "R65") (pin "1") (pinfunction "1_1") (pintype "input"))
      (node (ref "U1") (pin "24") (pinfunction "PB11_24") (pintype "unspecified"))
    )
    (net (code "18") (name "/L_OUT") (class "Default")
      (node (ref "C75") (pin "2") (pinfunction "2_2") (pintype "input"))
      (node (ref "U20") (pin "3") (pinfunction "3_3") (pintype "unspecified"))
    )
    (net (code "19") (name "/NRST") (class "Default")
      (node (ref "C11") (pin "2") (pinfunction "2_2") (pintype "input"))
      (node (ref "R6") (pin "2") (pinfunction "2_2") (pintype "input"))
      (node (ref "SW1") (pin "1") (pinfunction "1_1") (pintype "input"))
      (node (ref "U1") (pin "7") (pinfunction "PG10-NRST_7") (pintype "unspecified"))
    )
    (net (code "20") (name "/OLED_RES") (class "Default")
      (node (ref "OLED1") (pin "14") (pinfunction "RES#_14") (pintype "input"))
      (node (ref "U1") (pin "32") (pinfunction "PA10_32") (pintype "unspecified"))
    )
    (net (code "21") (name "/OLED_SCL") (class "Default")
      (node (ref "OLED1") (pin "18") (pinfunction "D0_18") (pintype "input"))
      (node (ref "R68") (pin "1") (pinfunction "1_1") (pintype "input"))
      (node (ref "U1") (pin "38") (pinfunction "PA15_38") (pintype "unspecified"))
    )
    (net (code "22") (name "/OLED_SDA") (class "Default")
      (node (ref "OLED1") (pin "19") (pinfunction "D1_19") (pintype "input"))
      (node (ref "OLED1") (pin "20") (pinfunction "D2_20") (pintype "input"))
      (node (ref "R67") (pin "1") (pinfunction "1_1") (pintype "input"))
      (node (ref "U1") (pin "45") (pinfunction "PB7_45") (pintype "unspecified"))
    )
    (net (code "23") (name "/OSC_IN") (class "Default")
      (node (ref "C12") (pin "2") (pinfunction "2_2") (pintype "input"))
      (node (ref "U1") (pin "5") (pinfunction "PF0-OSC_IN_5") (pintype "unspecified"))
      (node (ref "X2") (pin "1") (pinfunction "1_1") (pintype "input"))
    )
    (net (code "24") (name "/OSC_OUT") (class "Default")
      (node (ref "C13") (pin "2") (pinfunction "2_2") (pintype "input"))
      (node (ref "U1") (pin "6") (pinfunction "PF1-OSC_OUT_6") (pintype "unspecified"))
      (node (ref "X2") (pin "3") (pinfunction "3_3") (pintype "input"))
    )
    (net (code "25") (name "/OUTA+") (class "Default")
      (node (ref "R15") (pin "1") (pinfunction "1_1") (pintype "input"))
      (node (ref "U9") (pin "23") (pinfunction "AOUTA+_23") (pintype "input"))
    )
    (net (code "26") (name "/OUTA-") (class "Default")
      (node (ref "R14") (pin "1") (pinfunction "1_1") (pintype "input"))
      (node (ref "U9") (pin "24") (pinfunction "AOUTA-_24") (pintype "input"))
    )
    (net (code "27") (name "/OUTB+") (class "Default")
      (node (ref "R16") (pin "1") (pinfunction "1_1") (pintype "input"))
      (node (ref "U9") (pin "20") (pinfunction "AOUTB+_20") (pintype "input"))
    )
    (net (code "28") (name "/OUTB-") (class "Default")
      (node (ref "R17") (pin "1") (pinfunction "1_1") (pintype "input"))
      (node (ref "U9") (pin "19") (pinfunction "AOUTB-_19") (pintype "input"))
    )
    (net (code "29") (name "/R_OUT") (class "Default")
      (node (ref "C76") (pin "2") (pinfunction "2_2") (pintype "input"))
      (node (ref "U20") (pin "4") (pinfunction "4_4") (pintype "unspecified"))
    )
    (net (code "30") (name "/SWCLK") (class "Default")
      (node (ref "CN2") (pin "3") (pinfunction "3_3") (pintype "unspecified"))
      (node (ref "U1") (pin "37") (pinfunction "PA14_37") (pintype "unspecified"))
    )
    (net (code "31") (name "/SWDIO") (class "Default")
      (node (ref "CN2") (pin "4") (pinfunction "4_4") (pintype "unspecified"))
      (node (ref "U1") (pin "36") (pinfunction "PA13_36") (pintype "unspecified"))
    )
    (net (code "32") (name "/UART_RX") (class "Default")
      (node (ref "U1") (pin "11") (pinfunction "PA3_11") (pintype "unspecified"))
    )
    (net (code "33") (name "/UART_TX") (class "Default")
      (node (ref "U1") (pin "10") (pinfunction "PA2_10") (pintype "unspecified"))
    )
    (net (code "34") (name "/USB+") (class "Default")
      (node (ref "R2") (pin "2") (pinfunction "2_2") (pintype "input"))
      (node (ref "R60") (pin "1") (pinfunction "1_1") (pintype "input"))
      (node (ref "USB1") (pin "6") (pinfunction "DP1_6") (pintype "unspecified"))
      (node (ref "USB1") (pin "8") (pinfunction "DP2_8") (pintype "unspecified"))
    )
    (net (code "35") (name "/USB-") (class "Default")
      (node (ref "R61") (pin "1") (pinfunction "1_1") (pintype "input"))
      (node (ref "USB1") (pin "5") (pinfunction "DN2_5") (pintype "unspecified"))
      (node (ref "USB1") (pin "7") (pinfunction "DN1_7") (pintype "unspecified"))
    )
    (net (code "36") (name "/VA") (class "Default")
      (node (ref "C16") (pin "1") (pinfunction "1_1") (pintype "input"))
      (node (ref "C17") (pin "1") (pinfunction "1_1") (pintype "input"))
      (node (ref "C56") (pin "2") (pinfunction "2_2") (pintype "input"))
      (node (ref "C58") (pin "2") (pinfunction "2_2") (pintype "input"))
      (node (ref "U13") (pin "5") (pinfunction "OUT_5") (pintype "input"))
      (node (ref "U9") (pin "17") (pinfunction "VREF_17") (pintype "input"))
      (node (ref "U9") (pin "22") (pinfunction "VA_22") (pintype "input"))
    )
    (net (code "37") (name "/VCC12") (class "Default")
      (node (ref "C65") (pin "2") (pinfunction "2_2") (pintype "input"))
      (node (ref "C66") (pin "2") (pinfunction "2_2") (pintype "input"))
      (node (ref "D1") (pin "1") (pinfunction "A_1") (pintype "unspecified"))
      (node (ref "R52") (pin "2") (pinfunction "2_2") (pintype "input"))
      (node (ref "U19") (pin "3") (pinfunction "INPUT_3") (pintype "unspecified"))
    )
    (net (code "38") (name "AGND") (class "Default")
      (node (ref "C16") (pin "2") (pinfunction "2_2") (pintype "input"))
      (node (ref "C17") (pin "2") (pinfunction "2_2") (pintype "input"))
      (node (ref "C18") (pin "2") (pinfunction "2_2") (pintype "input"))
      (node (ref "C19") (pin "2") (pinfunction "2_2") (pintype "input"))
      (node (ref "C20") (pin "1") (pinfunction "1_1") (pintype "input"))
      (node (ref "C21") (pin "2") (pinfunction "2_2") (pintype "input"))
      (node (ref "C22") (pin "1") (pinfunction "1_1") (pintype "input"))
      (node (ref "C23") (pin "2") (pinfunction "2_2") (pintype "input"))
      (node (ref "C24") (pin "1") (pinfunction "1_1") (pintype "input"))
      (node (ref "C25") (pin "2") (pinfunction "2_2") (pintype "input"))
      (node (ref "C26") (pin "1") (pinfunction "1_1") (pintype "input"))
      (node (ref "C56") (pin "1") (pinfunction "1_1") (pintype "input"))
      (node (ref "C58") (pin "1") (pinfunction "1_1") (pintype "input"))
      (node (ref "C59") (pin "2") (pinfunction "2_2") (pintype "input"))
      (node (ref "C63") (pin "2") (pinfunction "2_2") (pintype "input"))
      (node (ref "CN3") (pin "1") (pinfunction "1_1") (pintype "unspecified"))
      (node (ref "CN3") (pin "2") (pinfunction "2_2") (pintype "unspecified"))
      (node (ref "P9") (pin "1") (pinfunction "1_1") (pintype "input"))
      (node (ref "R1") (pin "1") (pinfunction "1_1") (pintype "unspecified"))
      (node (ref "R44") (pin "1") (pinfunction "1_1") (pintype "input"))
      (node (ref "R47") (pin "1") (pinfunction "1_1") (pintype "input"))
      (node (ref "R50") (pin "1") (pinfunction "1_1") (pintype "input"))
      (node (ref "R58") (pin "1") (pinfunction "1_1") (pintype "unspecified"))
      (node (ref "U14") (pin "6") (pinfunction "V-_6") (pintype "unspecified"))
      (node (ref "U15") (pin "2") (pinfunction "V-_2") (pintype "unspecified"))
      (node (ref "U16") (pin "6") (pinfunction "V-_6") (pintype "unspecified"))
      (node (ref "U17") (pin "2") (pinfunction "V-_2") (pintype "unspecified"))
      (node (ref "U20") (pin "2") (pinfunction "2_2") (pintype "unspecified"))
      (node (ref "U9") (pin "16") (pinfunction "REF_GND_16") (pintype "input"))
      (node (ref "U9") (pin "21") (pinfunction "AGND_21") (pintype "input"))
    )
    (net (code "39") (name "GND") (class "Default")
      (node (ref "C1") (pin "1") (pinfunction "1_1") (pintype "input"))
      (node (ref "C10") (pin "1") (pinfunction "1_1") (pintype "input"))
      (node (ref "C11") (pin "1") (pinfunction "1_1") (pintype "input"))
      (node (ref "C12") (pin "1") (pinfunction "1_1") (pintype "input"))
      (node (ref "C13") (pin "1") (pinfunction "1_1") (pintype "input"))
      (node (ref "C2") (pin "1") (pinfunction "1_1") (pintype "input"))
      (node (ref "C55") (pin "1") (pinfunction "1_1") (pintype "input"))
      (node (ref "C57") (pin "2") (pinfunction "2_2") (pintype "input"))
      (node (ref "C60") (pin "1") (pinfunction "1_1") (pintype "input"))
      (node (ref "C61") (pin "2") (pinfunction "2_2") (pintype "input"))
      (node (ref "C62") (pin "2") (pinfunction "2_2") (pintype "input"))
      (node (ref "C64") (pin "1") (pinfunction "1_1") (pintype "input"))
      (node (ref "C65") (pin "1") (pinfunction "1_1") (pintype "input"))
      (node (ref "C66") (pin "1") (pinfunction "1_1") (pintype "input"))
      (node (ref "C67") (pin "1") (pinfunction "1_1") (pintype "input"))
      (node (ref "C68") (pin "1") (pinfunction "1_1") (pintype "input"))
      (node (ref "C69") (pin "1") (pinfunction "1_1") (pintype "input"))
      (node (ref "C7") (pin "1") (pinfunction "1_1") (pintype "input"))
      (node (ref "C70") (pin "1") (pinfunction "1_1") (pintype "input"))
      (node (ref "C71") (pin "1") (pinfunction "1_1") (pintype "input"))
      (node (ref "C72") (pin "1") (pinfunction "1_1") (pintype "input"))
      (node (ref "C77") (pin "1") (pinfunction "1_1") (pintype "input"))
      (node (ref "C8") (pin "1") (pinfunction "1_1") (pintype "input"))
      (node (ref "C9") (pin "1") (pinfunction "1_1") (pintype "input"))
      (node (ref "CN2") (pin "2") (pinfunction "2_2") (pintype "unspecified"))
      (node (ref "OLED1") (pin "1") (pinfunction "N.C.(GND)_1") (pintype "input"))
      (node (ref "OLED1") (pin "10") (pinfunction "BS0_10") (pintype "input"))
      (node (ref "OLED1") (pin "12") (pinfunction "BS2_12") (pintype "input"))
      (node (ref "OLED1") (pin "13") (pinfunction "CS#_13") (pintype "input"))
      (node (ref "OLED1") (pin "15") (pinfunction "D/C#_15") (pintype "input"))
      (node (ref "OLED1") (pin "16") (pinfunction "R/W#_16") (pintype "input"))
      (node (ref "OLED1") (pin "17") (pinfunction "E/RD#_17") (pintype "input"))
      (node (ref "OLED1") (pin "21") (pinfunction "D3_21") (pintype "input"))
      (node (ref "OLED1") (pin "22") (pinfunction "D4_22") (pintype "input"))
      (node (ref "OLED1") (pin "23") (pinfunction "D5_23") (pintype "input"))
      (node (ref "OLED1") (pin "24") (pinfunction "D6_24") (pintype "input"))
      (node (ref "OLED1") (pin "25") (pinfunction "D7_25") (pintype "input"))
      (node (ref "OLED1") (pin "29") (pinfunction "VLSS_29") (pintype "input"))
      (node (ref "OLED1") (pin "30") (pinfunction "N.C.(GND)_30") (pintype "input"))
      (node (ref "OLED1") (pin "8") (pinfunction "VSS_8") (pintype "input"))
      (node (ref "P8") (pin "1") (pinfunction "1_1") (pintype "input"))
      (node (ref "R3") (pin "2") (pinfunction "2_2") (pintype "input"))
      (node (ref "R4") (pin "2") (pinfunction "2_2") (pintype "input"))
      (node (ref "R44") (pin "2") (pinfunction "2_2") (pintype "input"))
      (node (ref "R53") (pin "1") (pinfunction "1_1") (pintype "input"))
      (node (ref "R56") (pin "1") (pinfunction "1_1") (pintype "unspecified"))
      (node (ref "R57") (pin "2") (pinfunction "2_2") (pintype "input"))
      (node (ref "R62") (pin "1") (pinfunction "1_1") (pintype "input"))
      (node (ref "R63") (pin "1") (pinfunction "1_1") (pintype "input"))
      (node (ref "R7") (pin "2") (pinfunction "2_2") (pintype "input"))
      (node (ref "SW1") (pin "2") (pinfunction "2_2") (pintype "input"))
      (node (ref "SW2") (pin "2") (pinfunction "2_2") (pintype "input"))
      (node (ref "U1") (pin "49") (pinfunction "EP_49") (pintype "unspecified"))
      (node (ref "U13") (pin "2") (pinfunction "GND_2") (pintype "input"))
      (node (ref "U18") (pin "2") (pinfunction "GND_2") (pintype "input"))
      (node (ref "U5") (pin "2") (pinfunction "GND_2") (pintype "input"))
      (node (ref "U9") (pin "12") (pinfunction "M0(AD0/CS#)_12") (pintype "input"))
      (node (ref "U9") (pin "8") (pinfunction "DGND_8") (pintype "input"))
      (node (ref "U9") (pin "9") (pinfunction "M3(AD1/CDIN)_9") (pintype "input"))
      (node (ref "USB1") (pin "1") (pinfunction "GND_1") (pintype "unspecified"))
      (node (ref "USB1") (pin "12") (pinfunction "GND_12") (pintype "unspecified"))
      (node (ref "X2") (pin "2") (pinfunction "GND_2") (pintype "input"))
      (node (ref "X2") (pin "4") (pinfunction "GND_4") (pintype "input"))
    )
    (net (code "40") (name "Net-(C19-Pad1)") (class "Default")
      (node (ref "C19") (pin "1") (pinfunction "1_1") (pintype "input"))
      (node (ref "R14") (pin "2") (pinfunction "2_2") (pintype "input"))
      (node (ref "R18") (pin "1") (pinfunction "1_1") (pintype "input"))
    )
    (net (code "41") (name "Net-(C20-Pad2)") (class "Default")
      (node (ref "C20") (pin "2") (pinfunction "2_2") (pintype "input"))
      (node (ref "R15") (pin "2") (pinfunction "2_2") (pintype "input"))
      (node (ref "R19") (pin "1") (pinfunction "1_1") (pintype "input"))
    )
    (net (code "42") (name "Net-(C21-Pad1)") (class "Default")
      (node (ref "C21") (pin "1") (pinfunction "1_1") (pintype "input"))
      (node (ref "R16") (pin "2") (pinfunction "2_2") (pintype "input"))
      (node (ref "R20") (pin "1") (pinfunction "1_1") (pintype "input"))
    )
    (net (code "43") (name "Net-(C22-Pad2)") (class "Default")
      (node (ref "C22") (pin "2") (pinfunction "2_2") (pintype "input"))
      (node (ref "R17") (pin "2") (pinfunction "2_2") (pintype "input"))
      (node (ref "R21") (pin "1") (pinfunction "1_1") (pintype "input"))
    )
    (net (code "44") (name "Net-(C23-Pad1)") (class "Default")
      (node (ref "C23") (pin "1") (pinfunction "1_1") (pintype "input"))
      (node (ref "C28") (pin "1") (pinfunction "1_1") (pintype "input"))
      (node (ref "R18") (pin "2") (pinfunction "2_2") (pintype "input"))
    )
    (net (code "45") (name "Net-(C24-Pad2)") (class "Default")
      (node (ref "C24") (pin "2") (pinfunction "2_2") (pintype "input"))
      (node (ref "C29") (pin "1") (pinfunction "1_1") (pintype "input"))
      (node (ref "R19") (pin "2") (pinfunction "2_2") (pintype "input"))
    )
    (net (code "46") (name "Net-(C25-Pad1)") (class "Default")
      (node (ref "C25") (pin "1") (pinfunction "1_1") (pintype "input"))
      (node (ref "C30") (pin "1") (pinfunction "1_1") (pintype "input"))
      (node (ref "R20") (pin "2") (pinfunction "2_2") (pintype "input"))
    )
    (net (code "47") (name "Net-(C26-Pad2)") (class "Default")
      (node (ref "C26") (pin "2") (pinfunction "2_2") (pintype "input"))
      (node (ref "C31") (pin "1") (pinfunction "1_1") (pintype "input"))
      (node (ref "R21") (pin "2") (pinfunction "2_2") (pintype "input"))
    )
    (net (code "48") (name "Net-(C75-Pad1)") (class "Default")
      (node (ref "C75") (pin "1") (pinfunction "1_1") (pintype "input"))
      (node (ref "R1") (pin "2") (pinfunction "2_2") (pintype "unspecified"))
    )
    (net (code "49") (name "Net-(C76-Pad1)") (class "Default")
      (node (ref "C76") (pin "1") (pinfunction "1_1") (pintype "input"))
      (node (ref "R58") (pin "2") (pinfunction "2_2") (pintype "unspecified"))
    )
    (net (code "50") (name "Net-(D1-K)") (class "Default")
      (node (ref "D1") (pin "2") (pinfunction "K_2") (pintype "unspecified"))
      (node (ref "L2") (pin "2") (pinfunction "2_2") (pintype "unspecified"))
      (node (ref "U18") (pin "1") (pinfunction "SW_1") (pintype "input"))
    )
    (net (code "51") (name "Net-(D2-K)") (class "Default")
      (node (ref "C67") (pin "2") (pinfunction "2_2") (pintype "input"))
      (node (ref "D2") (pin "2") (pinfunction "K_2") (pintype "unspecified"))
      (node (ref "R55") (pin "1") (pinfunction "1_1") (pintype "input"))
      (node (ref "R56") (pin "2") (pinfunction "2_2") (pintype "unspecified"))
      (node (ref "U19") (pin "1") (pinfunction "ADJUST_1") (pintype "unspecified"))
    )
    (net (code "52") (name "Net-(OLED1-C1N)") (class "Default")
      (node (ref "C73") (pin "1") (pinfunction "1_1") (pintype "input"))
      (node (ref "OLED1") (pin "5") (pinfunction "C1N_5") (pintype "input"))
    )
    (net (code "53") (name "Net-(OLED1-C1P)") (class "Default")
      (node (ref "C73") (pin "2") (pinfunction "2_2") (pintype "input"))
      (node (ref "OLED1") (pin "4") (pinfunction "C1P_4") (pintype "input"))
    )
    (net (code "54") (name "Net-(OLED1-C2N)") (class "Default")
      (node (ref "C74") (pin "1") (pinfunction "1_1") (pintype "input"))
      (node (ref "OLED1") (pin "3") (pinfunction "C2N_3") (pintype "input"))
    )
    (net (code "55") (name "Net-(OLED1-C2P)") (class "Default")
      (node (ref "C74") (pin "2") (pinfunction "2_2") (pintype "input"))
      (node (ref "OLED1") (pin "2") (pinfunction "C2P_2") (pintype "input"))
    )
    (net (code "56") (name "Net-(OLED1-IREF)") (class "Default")
      (node (ref "OLED1") (pin "26") (pinfunction "IREF_26") (pintype "input"))
      (node (ref "R57") (pin "1") (pinfunction "1_1") (pintype "input"))
    )
    (net (code "57") (name "Net-(OLED1-VCC)") (class "Default")
      (node (ref "C71") (pin "2") (pinfunction "2_2") (pintype "input"))
      (node (ref "OLED1") (pin "28") (pinfunction "VCC_28") (pintype "input"))
    )
    (net (code "58") (name "Net-(OLED1-VCOMH)") (class "Default")
      (node (ref "C72") (pin "2") (pinfunction "2_2") (pintype "input"))
      (node (ref "OLED1") (pin "27") (pinfunction "VCOMH_27") (pintype "input"))
    )
    (net (code "59") (name "Net-(P2-Pad1)") (class "Default")
      (node (ref "P2") (pin "1") (pinfunction "1_1") (pintype "input"))
      (node (ref "R62") (pin "2") (pinfunction "2_2") (pintype "input"))
    )
    (net (code "60") (name "Net-(P4-Pad1)") (class "Default")
      (node (ref "P4") (pin "1") (pinfunction "1_1") (pintype "input"))
      (node (ref "R63") (pin "2") (pinfunction "2_2") (pintype "input"))
    )
    (net (code "61") (name "Net-(U1-PA11)") (class "Default")
      (node (ref "R61") (pin "2") (pinfunction "2_2") (pintype "input"))
      (node (ref "U1") (pin "33") (pinfunction "PA11_33") (pintype "unspecified"))
    )
    (net (code "62") (name "Net-(U1-PA12)") (class "Default")
      (node (ref "R60") (pin "2") (pinfunction "2_2") (pintype "input"))
      (node (ref "U1") (pin "34") (pinfunction "PA12_34") (pintype "unspecified"))
    )
    (net (code "63") (name "Net-(U1-PB8-BOOT0)") (class "Default")
      (node (ref "R7") (pin "1") (pinfunction "1_1") (pintype "input"))
      (node (ref "U1") (pin "46") (pinfunction "PB8-BOOT0_46") (pintype "unspecified"))
    )
    (net (code "64") (name "Net-(U9-FILT+)") (class "Default")
      (node (ref "C18") (pin "1") (pinfunction "1_1") (pintype "input"))
      (node (ref "C59") (pin "1") (pinfunction "1_1") (pintype "input"))
      (node (ref "U9") (pin "15") (pinfunction "FILT+_15") (pintype "input"))
    )
    (net (code "65") (name "Net-(U9-VQ)") (class "Default")
      (node (ref "C63") (pin "1") (pinfunction "1_1") (pintype "input"))
      (node (ref "U9") (pin "26") (pinfunction "VQ_26") (pintype "input"))
    )
    (net (code "66") (name "Net-(U14-GS1)") (class "Default")
      (node (ref "R45") (pin "1") (pinfunction "1_1") (pintype "input"))
      (node (ref "U14") (pin "3") (pinfunction "GS1_3") (pintype "unspecified"))
    )
    (net (code "67") (name "Net-(U14-GS2)") (class "Default")
      (node (ref "R45") (pin "2") (pinfunction "2_2") (pintype "input"))
      (node (ref "U14") (pin "12") (pinfunction "GS2_12") (pintype "unspecified"))
    )
    (net (code "68") (name "Net-(U14-Ref)") (class "Default")
      (node (ref "U14") (pin "10") (pinfunction "Ref_10") (pintype "unspecified"))
      (node (ref "U15") (pin "1") (pinfunction "OUT_1") (pintype "output"))
      (node (ref "U15") (pin "4") (pinfunction "IN-_4") (pintype "unspecified"))
    )
    (net (code "69") (name "Net-(U14-Sense)") (class "Default")
      (node (ref "P5") (pin "1") (pinfunction "1_1") (pintype "input"))
      (node (ref "R1") (pin "3") (pinfunction "3_3") (pintype "unspecified"))
      (node (ref "U14") (pin "8") (pinfunction "Sense_8") (pintype "unspecified"))
      (node (ref "U14") (pin "9") (pinfunction "VO_9") (pintype "unspecified"))
    )
    (net (code "70") (name "Net-(U15-IN+)") (class "Default")
      (node (ref "R46") (pin "1") (pinfunction "1_1") (pintype "input"))
      (node (ref "R47") (pin "2") (pinfunction "2_2") (pintype "input"))
      (node (ref "U15") (pin "3") (pinfunction "IN+_3") (pintype "unspecified"))
    )
    (net (code "71") (name "Net-(U16-GS1)") (class "Default")
      (node (ref "R48") (pin "1") (pinfunction "1_1") (pintype "input"))
      (node (ref "U16") (pin "3") (pinfunction "GS1_3") (pintype "unspecified"))
    )
    (net (code "72") (name "Net-(U16-GS2)") (class "Default")
      (node (ref "R48") (pin "2") (pinfunction "2_2") (pintype "input"))
      (node (ref "U16") (pin "12") (pinfunction "GS2_12") (pintype "unspecified"))
    )
    (net (code "73") (name "Net-(U16-Ref)") (class "Default")
      (node (ref "U16") (pin "10") (pinfunction "Ref_10") (pintype "unspecified"))
      (node (ref "U17") (pin "1") (pinfunction "OUT_1") (pintype "output"))
      (node (ref "U17") (pin "4") (pinfunction "IN-_4") (pintype "unspecified"))
    )
    (net (code "74") (name "Net-(U16-Sense)") (class "Default")
      (node (ref "P6") (pin "1") (pinfunction "1_1") (pintype "input"))
      (node (ref "R58") (pin "3") (pinfunction "3_3") (pintype "unspecified"))
      (node (ref "U16") (pin "8") (pinfunction "Sense_8") (pintype "unspecified"))
      (node (ref "U16") (pin "9") (pinfunction "VO_9") (pintype "unspecified"))
    )
    (net (code "75") (name "Net-(U17-IN+)") (class "Default")
      (node (ref "R49") (pin "1") (pinfunction "1_1") (pintype "input"))
      (node (ref "R50") (pin "2") (pinfunction "2_2") (pintype "input"))
      (node (ref "U17") (pin "3") (pinfunction "IN+_3") (pintype "unspecified"))
    )
    (net (code "76") (name "Net-(U18-EN)") (class "Default")
      (node (ref "R51") (pin "1") (pinfunction "1_1") (pintype "input"))
      (node (ref "U18") (pin "4") (pinfunction "EN_4") (pintype "input"))
    )
    (net (code "77") (name "Net-(U18-FB)") (class "Default")
      (node (ref "R52") (pin "1") (pinfunction "1_1") (pintype "input"))
      (node (ref "R53") (pin "2") (pinfunction "2_2") (pintype "input"))
      (node (ref "U18") (pin "3") (pinfunction "FB_3") (pintype "input"))
    )
    (net (code "78") (name "Net-(U22-B)") (class "Default")
      (node (ref "R64") (pin "2") (pinfunction "2_2") (pintype "input"))
      (node (ref "U22") (pin "1") (pinfunction "B_1") (pintype "unspecified"))
    )
    (net (code "79") (name "Net-(U22-C)") (class "Default")
      (node (ref "P1") (pin "1") (pinfunction "1_1") (pintype "input"))
      (node (ref "U22") (pin "3") (pinfunction "C_3") (pintype "unspecified"))
    )
    (net (code "80") (name "Net-(U23-B)") (class "Default")
      (node (ref "R65") (pin "2") (pinfunction "2_2") (pintype "input"))
      (node (ref "U23") (pin "1") (pinfunction "B_1") (pintype "unspecified"))
    )
    (net (code "81") (name "Net-(U23-C)") (class "Default")
      (node (ref "P3") (pin "1") (pinfunction "1_1") (pintype "input"))
      (node (ref "U23") (pin "3") (pinfunction "C_3") (pintype "unspecified"))
    )
    (net (code "82") (name "Net-(USB1-CC1)") (class "Default")
      (node (ref "R4") (pin "1") (pinfunction "1_1") (pintype "input"))
      (node (ref "USB1") (pin "4") (pinfunction "CC1_4") (pintype "unspecified"))
    )
    (net (code "83") (name "Net-(USB1-CC2)") (class "Default")
      (node (ref "R3") (pin "1") (pinfunction "1_1") (pintype "input"))
      (node (ref "USB1") (pin "10") (pinfunction "CC2_10") (pintype "unspecified"))
    )
    (net (code "84") (name "VCC3.3") (class "Default")
      (node (ref "C10") (pin "2") (pinfunction "2_2") (pintype "input"))
      (node (ref "C2") (pin "2") (pinfunction "2_2") (pintype "input"))
      (node (ref "C57") (pin "1") (pinfunction "1_1") (pintype "input"))
      (node (ref "C60") (pin "2") (pinfunction "2_2") (pintype "input"))
      (node (ref "C61") (pin "1") (pinfunction "1_1") (pintype "input"))
      (node (ref "C62") (pin "1") (pinfunction "1_1") (pintype "input"))
      (node (ref "C69") (pin "2") (pinfunction "2_2") (pintype "input"))
      (node (ref "C7") (pin "2") (pinfunction "2_2") (pintype "input"))
      (node (ref "C70") (pin "2") (pinfunction "2_2") (pintype "input"))
      (node (ref "C8") (pin "2") (pinfunction "2_2") (pintype "input"))
      (node (ref "C9") (pin "2") (pinfunction "2_2") (pintype "input"))
      (node (ref "CN2") (pin "1") (pinfunction "1_1") (pintype "unspecified"))
      (node (ref "OLED1") (pin "11") (pinfunction "BS1_11") (pintype "input"))
      (node (ref "OLED1") (pin "6") (pinfunction "VBAT_6") (pintype "input"))
      (node (ref "OLED1") (pin "9") (pinfunction "VDD_9") (pintype "input"))
      (node (ref "R2") (pin "1") (pinfunction "1_1") (pintype "input"))
      (node (ref "R43") (pin "1") (pinfunction "1_1") (pintype "input"))
      (node (ref "R59") (pin "1") (pinfunction "1_1") (pintype "input"))
      (node (ref "R6") (pin "1") (pinfunction "1_1") (pintype "input"))
      (node (ref "R66") (pin "1") (pinfunction "1_1") (pintype "input"))
      (node (ref "R67") (pin "2") (pinfunction "2_2") (pintype "input"))
      (node (ref "R68") (pin "2") (pinfunction "2_2") (pintype "input"))
      (node (ref "U1") (pin "1") (pinfunction "VBAT_1") (pintype "unspecified"))
      (node (ref "U1") (pin "20") (pinfunction "VREF+_20") (pintype "unspecified"))
      (node (ref "U1") (pin "21") (pinfunction "VDDA_21") (pintype "unspecified"))
      (node (ref "U1") (pin "23") (pinfunction "VDD_23") (pintype "unspecified"))
      (node (ref "U1") (pin "35") (pinfunction "VDD_35") (pintype "unspecified"))
      (node (ref "U1") (pin "48") (pinfunction "VDD_48") (pintype "unspecified"))
      (node (ref "U22") (pin "2") (pinfunction "E_2") (pintype "unspecified"))
      (node (ref "U23") (pin "2") (pinfunction "E_2") (pintype "unspecified"))
      (node (ref "U5") (pin "5") (pinfunction "OUT_5") (pintype "input"))
      (node (ref "U9") (pin "14") (pinfunction "VLC_14") (pintype "input"))
      (node (ref "U9") (pin "27") (pinfunction "VLS_27") (pintype "input"))
      (node (ref "U9") (pin "7") (pinfunction "VD_7") (pintype "input"))
    )
    (net (code "85") (name "VCC_OP") (class "Default")
      (node (ref "C68") (pin "2") (pinfunction "2_2") (pintype "input"))
      (node (ref "D2") (pin "1") (pinfunction "A_1") (pintype "unspecified"))
      (node (ref "P10") (pin "1") (pinfunction "1_1") (pintype "input"))
      (node (ref "R46") (pin "2") (pinfunction "2_2") (pintype "input"))
      (node (ref "R49") (pin "2") (pinfunction "2_2") (pintype "input"))
      (node (ref "R55") (pin "2") (pinfunction "2_2") (pintype "input"))
      (node (ref "U14") (pin "11") (pinfunction "V+_11") (pintype "unspecified"))
      (node (ref "U15") (pin "5") (pinfunction "V+_5") (pintype "unspecified"))
      (node (ref "U16") (pin "11") (pinfunction "V+_11") (pintype "unspecified"))
      (node (ref "U17") (pin "5") (pinfunction "V+_5") (pintype "unspecified"))
      (node (ref "U19") (pin "2") (pinfunction "OUTPUT/2_2") (pintype "unspecified"))
      (node (ref "U19") (pin "4") (pinfunction "OUTPUT_4") (pintype "unspecified"))
      (node (ref "U20") (pin "1") (pinfunction "1_1") (pintype "unspecified"))
    )
    (net (code "86") (name "VIN") (class "Default")
      (node (ref "C1") (pin "2") (pinfunction "2_2") (pintype "input"))
      (node (ref "C55") (pin "2") (pinfunction "2_2") (pintype "input"))
      (node (ref "C64") (pin "2") (pinfunction "2_2") (pintype "input"))
      (node (ref "L2") (pin "1") (pinfunction "1_1") (pintype "unspecified"))
      (node (ref "P7") (pin "1") (pinfunction "1_1") (pintype "input"))
      (node (ref "R51") (pin "2") (pinfunction "2_2") (pintype "input"))
      (node (ref "U13") (pin "1") (pinfunction "IN_1") (pintype "input"))
      (node (ref "U13") (pin "3") (pinfunction "EN_3") (pintype "input"))
      (node (ref "U18") (pin "5") (pinfunction "IN_5") (pintype "input"))
      (node (ref "U5") (pin "1") (pinfunction "IN_1") (pintype "input"))
      (node (ref "U5") (pin "3") (pinfunction "EN_3") (pintype "input"))
      (node (ref "USB1") (pin "11") (pinfunction "VBUS_11") (pintype "unspecified"))
      (node (ref "USB1") (pin "2") (pinfunction "VBUS_2") (pintype "unspecified"))
    )
    (net (code "87") (name "unconnected-(CN2-Pad5)") (class "Default")
      (node (ref "CN2") (pin "5") (pinfunction "5_5") (pintype "unspecified+no_connect"))
    )
    (net (code "88") (name "unconnected-(CN2-Pad6)") (class "Default")
      (node (ref "CN2") (pin "6") (pinfunction "6_6") (pintype "unspecified+no_connect"))
    )
    (net (code "89") (name "unconnected-(OLED1-N.C.-Pad7)") (class "Default")
      (node (ref "OLED1") (pin "7") (pinfunction "N.C._7") (pintype "input+no_connect"))
    )
    (net (code "90") (name "unconnected-(R56-Pad3)") (class "Default")
      (node (ref "R56") (pin "3") (pinfunction "3_3") (pintype "unspecified+no_connect"))
    )
    (net (code "91") (name "unconnected-(U1-PA1-Pad9)") (class "Default")
      (node (ref "U1") (pin "9") (pinfunction "PA1_9") (pintype "unspecified"))
    )
    (net (code "92") (name "unconnected-(U1-PA4-Pad12)") (class "Default")
      (node (ref "U1") (pin "12") (pinfunction "PA4_12") (pintype "unspecified"))
    )
    (net (code "93") (name "unconnected-(U1-PA7-Pad15)") (class "Default")
      (node (ref "U1") (pin "15") (pinfunction "PA7_15") (pintype "unspecified"))
    )
    (net (code "94") (name "unconnected-(U1-PB0-Pad17)") (class "Default")
      (node (ref "U1") (pin "17") (pinfunction "PB0_17") (pintype "unspecified"))
    )
    (net (code "95") (name "unconnected-(U1-PB1-Pad18)") (class "Default")
      (node (ref "U1") (pin "18") (pinfunction "PB1_18") (pintype "unspecified"))
    )
    (net (code "96") (name "unconnected-(U1-PB2-Pad19)") (class "Default")
      (node (ref "U1") (pin "19") (pinfunction "PB2_19") (pintype "unspecified"))
    )
    (net (code "97") (name "unconnected-(U1-PB3-Pad41)") (class "Default")
      (node (ref "U1") (pin "41") (pinfunction "PB3_41") (pintype "unspecified"))
    )
    (net (code "98") (name "unconnected-(U1-PB4-Pad42)") (class "Default")
      (node (ref "U1") (pin "42") (pinfunction "PB4_42") (pintype "unspecified"))
    )
    (net (code "99") (name "unconnected-(U1-PB5-Pad43)") (class "Default")
      (node (ref "U1") (pin "43") (pinfunction "PB5_43") (pintype "unspecified"))
    )
    (net (code "100") (name "unconnected-(U1-PB6-Pad44)") (class "Default")
      (node (ref "U1") (pin "44") (pinfunction "PB6_44") (pintype "unspecified"))
    )
    (net (code "101") (name "unconnected-(U1-PB9-Pad47)") (class "Default")
      (node (ref "U1") (pin "47") (pinfunction "PB9_47") (pintype "unspecified"))
    )
    (net (code "102") (name "unconnected-(U1-PB14-Pad27)") (class "Default")
      (node (ref "U1") (pin "27") (pinfunction "PB14_27") (pintype "unspecified"))
    )
    (net (code "103") (name "unconnected-(U1-PC4-Pad16)") (class "Default")
      (node (ref "U1") (pin "16") (pinfunction "PC4_16") (pintype "unspecified"))
    )
    (net (code "104") (name "unconnected-(U1-PC10-Pad39)") (class "Default")
      (node (ref "U1") (pin "39") (pinfunction "PC10_39") (pintype "unspecified"))
    )
    (net (code "105") (name "unconnected-(U1-PC11-Pad40)") (class "Default")
      (node (ref "U1") (pin "40") (pinfunction "PC11_40") (pintype "unspecified"))
    )
    (net (code "106") (name "unconnected-(U1-PC13-Pad2)") (class "Default")
      (node (ref "U1") (pin "2") (pinfunction "PC13_2") (pintype "unspecified"))
    )
    (net (code "107") (name "unconnected-(U1-PC14-OSC32_IN-Pad3)") (class "Default")
      (node (ref "U1") (pin "3") (pinfunction "PC14-OSC32_IN_3") (pintype "unspecified+no_connect"))
    )
    (net (code "108") (name "unconnected-(U1-PC15-OSC32_OUT-Pad4)") (class "Default")
      (node (ref "U1") (pin "4") (pinfunction "PC15-OSC32_OUT_4") (pintype "unspecified+no_connect"))
    )
    (net (code "109") (name "unconnected-(U5-NC{slash}FB-Pad4)") (class "Default")
      (node (ref "U5") (pin "4") (pinfunction "NC/FB_4") (pintype "input+no_connect"))
    )
    (net (code "110") (name "unconnected-(U9-AMUTEC-Pad25)") (class "Default")
      (node (ref "U9") (pin "25") (pinfunction "AMUTEC_25") (pintype "input+no_connect"))
    )
    (net (code "111") (name "unconnected-(U9-BMUTEC-Pad18)") (class "Default")
      (node (ref "U9") (pin "18") (pinfunction "BMUTEC_18") (pintype "input+no_connect"))
    )
    (net (code "112") (name "unconnected-(U9-DSD_A-Pad28)") (class "Default")
      (node (ref "U9") (pin "28") (pinfunction "DSD_A_28") (pintype "input+no_connect"))
    )
    (net (code "113") (name "unconnected-(U9-DSD_B-Pad1)") (class "Default")
      (node (ref "U9") (pin "1") (pinfunction "DSD_B_1") (pintype "input+no_connect"))
    )
    (net (code "114") (name "unconnected-(U9-DSD_SCLK-Pad2)") (class "Default")
      (node (ref "U9") (pin "2") (pinfunction "DSD_SCLK_2") (pintype "input+no_connect"))
    )
    (net (code "115") (name "unconnected-(U13-NC{slash}FB-Pad4)") (class "Default")
      (node (ref "U13") (pin "4") (pinfunction "NC/FB_4") (pintype "input+no_connect"))
    )
    (net (code "116") (name "unconnected-(U14-NC-Pad2)") (class "Default")
      (node (ref "U14") (pin "2") (pinfunction "NC_2") (pintype "unspecified+no_connect"))
    )
    (net (code "117") (name "unconnected-(U14-NC-Pad7)") (class "Default")
      (node (ref "U14") (pin "7") (pinfunction "NC_7") (pintype "unspecified+no_connect"))
    )
    (net (code "118") (name "unconnected-(U14-NC-Pad13)") (class "Default")
      (node (ref "U14") (pin "13") (pinfunction "NC_13") (pintype "unspecified+no_connect"))
    )
    (net (code "119") (name "unconnected-(U14-VO1-Pad1)") (class "Default")
      (node (ref "U14") (pin "1") (pinfunction "VO1_1") (pintype "unspecified+no_connect"))
    )
    (net (code "120") (name "unconnected-(U14-VO2-Pad14)") (class "Default")
      (node (ref "U14") (pin "14") (pinfunction "VO2_14") (pintype "unspecified+no_connect"))
    )
    (net (code "121") (name "unconnected-(U16-NC-Pad2)") (class "Default")
      (node (ref "U16") (pin "2") (pinfunction "NC_2") (pintype "unspecified+no_connect"))
    )
    (net (code "122") (name "unconnected-(U16-NC-Pad7)") (class "Default")
      (node (ref "U16") (pin "7") (pinfunction "NC_7") (pintype "unspecified+no_connect"))
    )
    (net (code "123") (name "unconnected-(U16-NC-Pad13)") (class "Default")
      (node (ref "U16") (pin "13") (pinfunction "NC_13") (pintype "unspecified+no_connect"))
    )
    (net (code "124") (name "unconnected-(U16-VO1-Pad1)") (class "Default")
      (node (ref "U16") (pin "1") (pinfunction "VO1_1") (pintype "unspecified+no_connect"))
    )
    (net (code "125") (name "unconnected-(U16-VO2-Pad14)") (class "Default")
      (node (ref "U16") (pin "14") (pinfunction "VO2_14") (pintype "unspecified+no_connect"))
    )
    (net (code "126") (name "unconnected-(U18-NC-Pad6)") (class "Default")
      (node (ref "U18") (pin "6") (pinfunction "NC_6") (pintype "input+no_connect"))
    )
    (net (code "127") (name "unconnected-(USB1-SBU1-Pad9)") (class "Default")
      (node (ref "USB1") (pin "9") (pinfunction "SBU1_9") (pintype "unspecified+no_connect"))
    )
    (net (code "128") (name "unconnected-(USB1-SBU2-Pad3)") (class "Default")
      (node (ref "USB1") (pin "3") (pinfunction "SBU2_3") (pintype "unspecified+no_connect"))
    )
    (net (code "129") (name "unconnected-(USB1-SHELL-Pad13)") (class "Default")
      (node (ref "USB1") (pin "13") (pinfunction "SHELL_13") (pintype "unspecified"))
    )
    (net (code "130") (name "unconnected-(USB1-SHELL-Pad14)") (class "Default")
      (node (ref "USB1") (pin "14") (pinfunction "SHELL_14") (pintype "unspecified"))
    )
  )
)
